# EK-TM4C1294XL_REV_D-shield.net
KiCad netlist of a schematic drawn in EAGLE
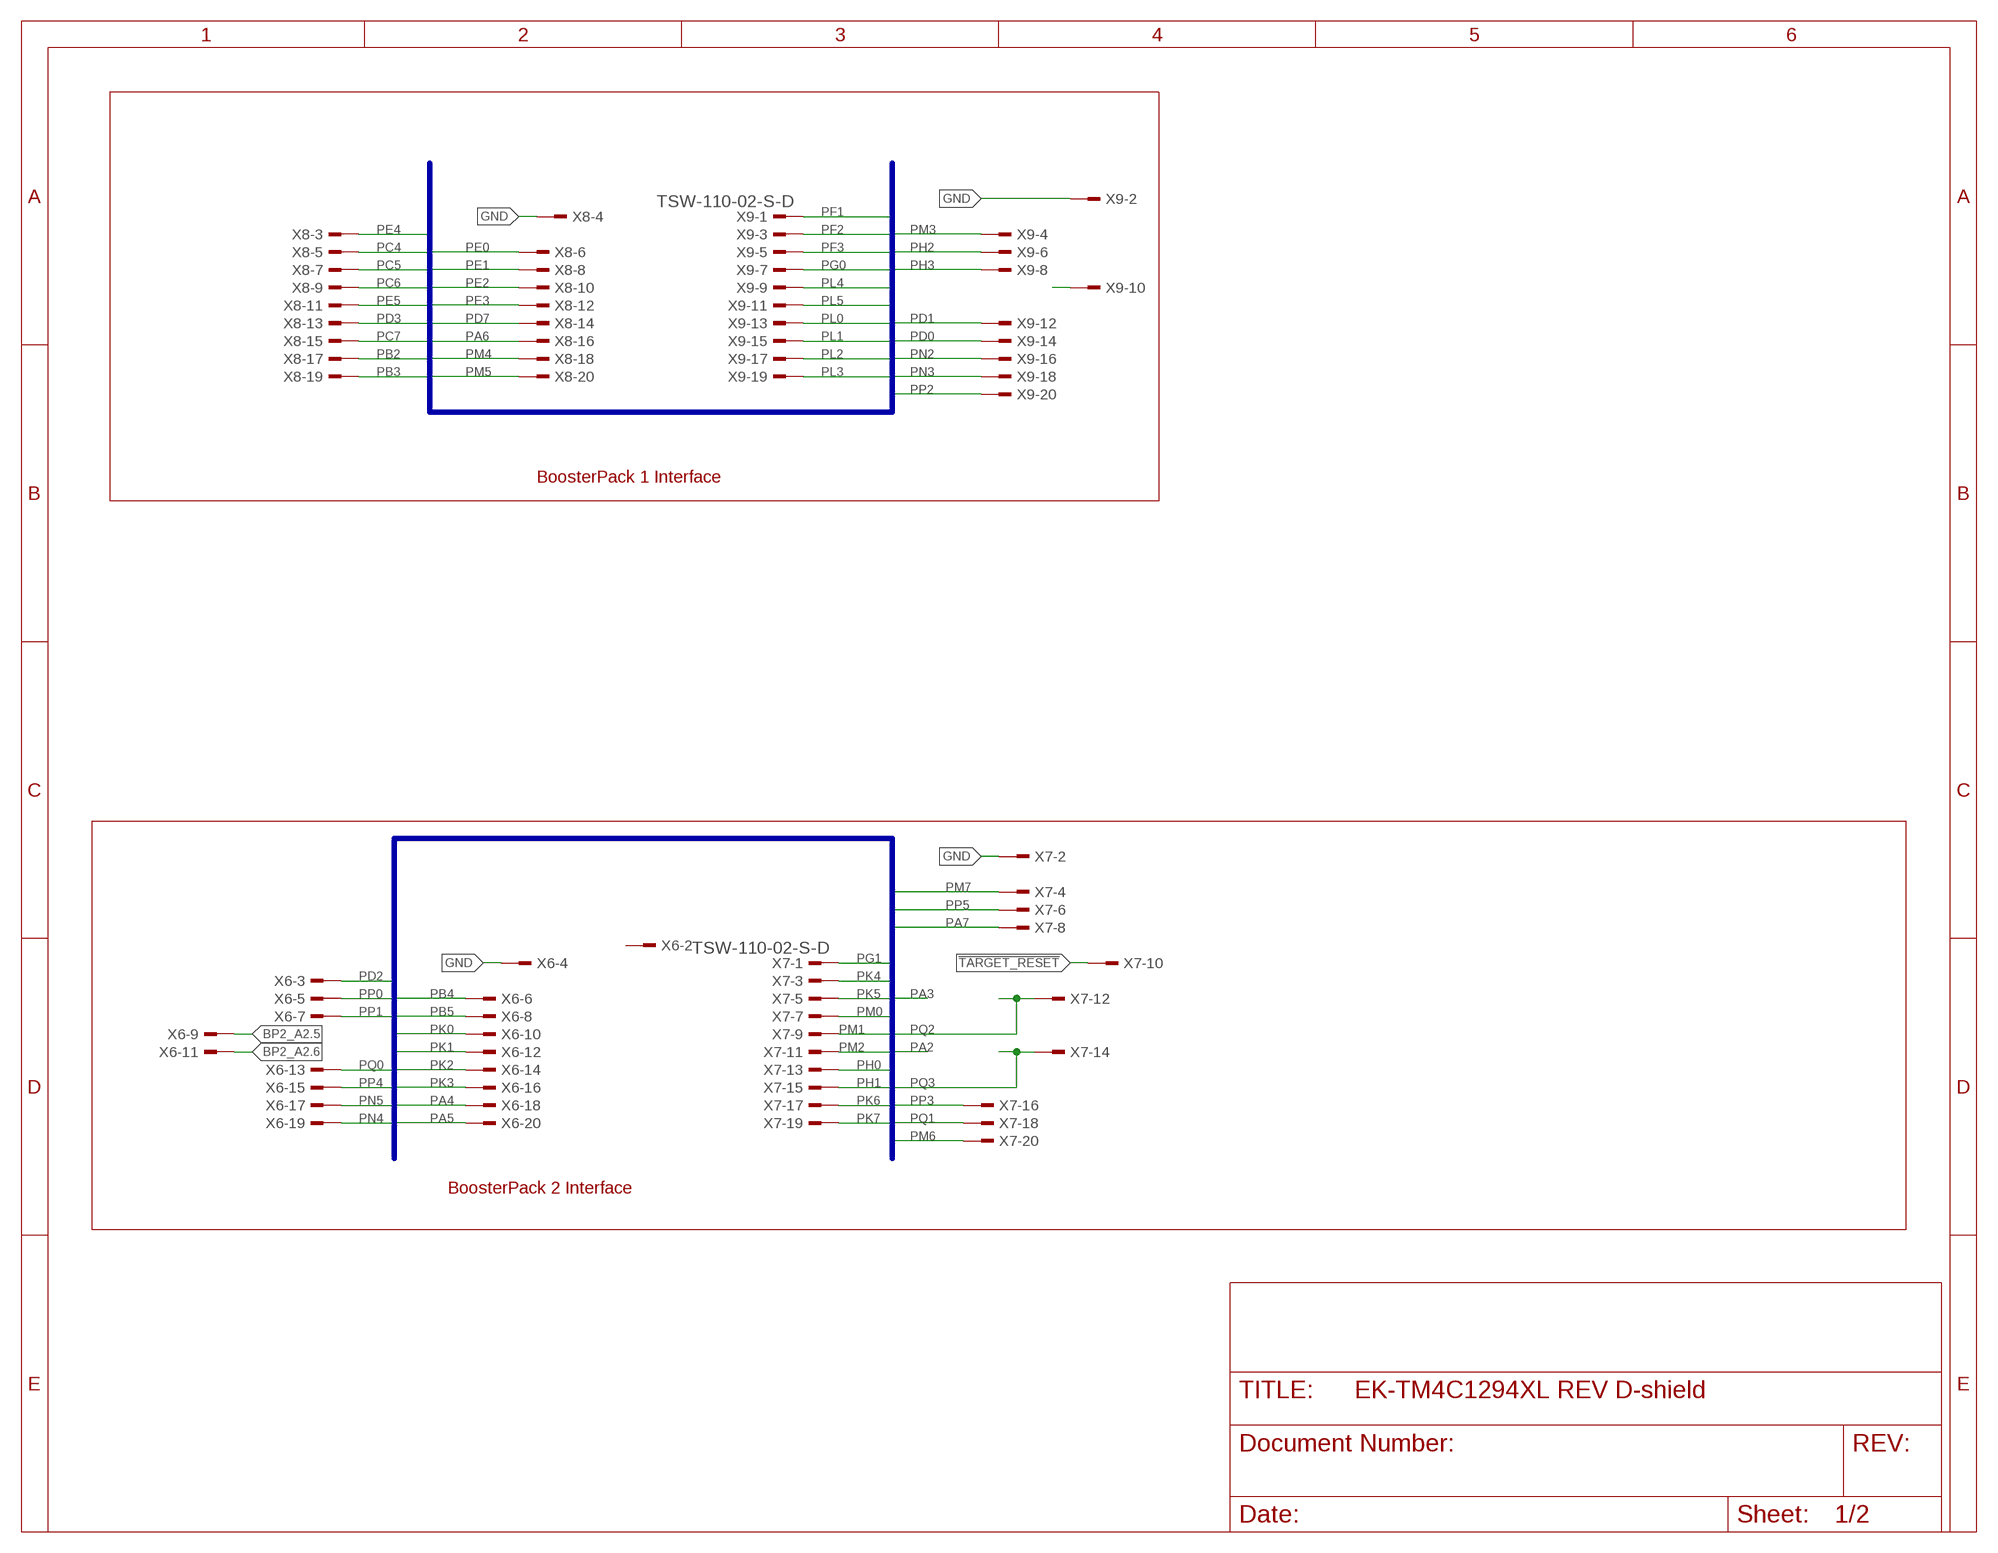
[diagram p0: schematic, sheet 1]
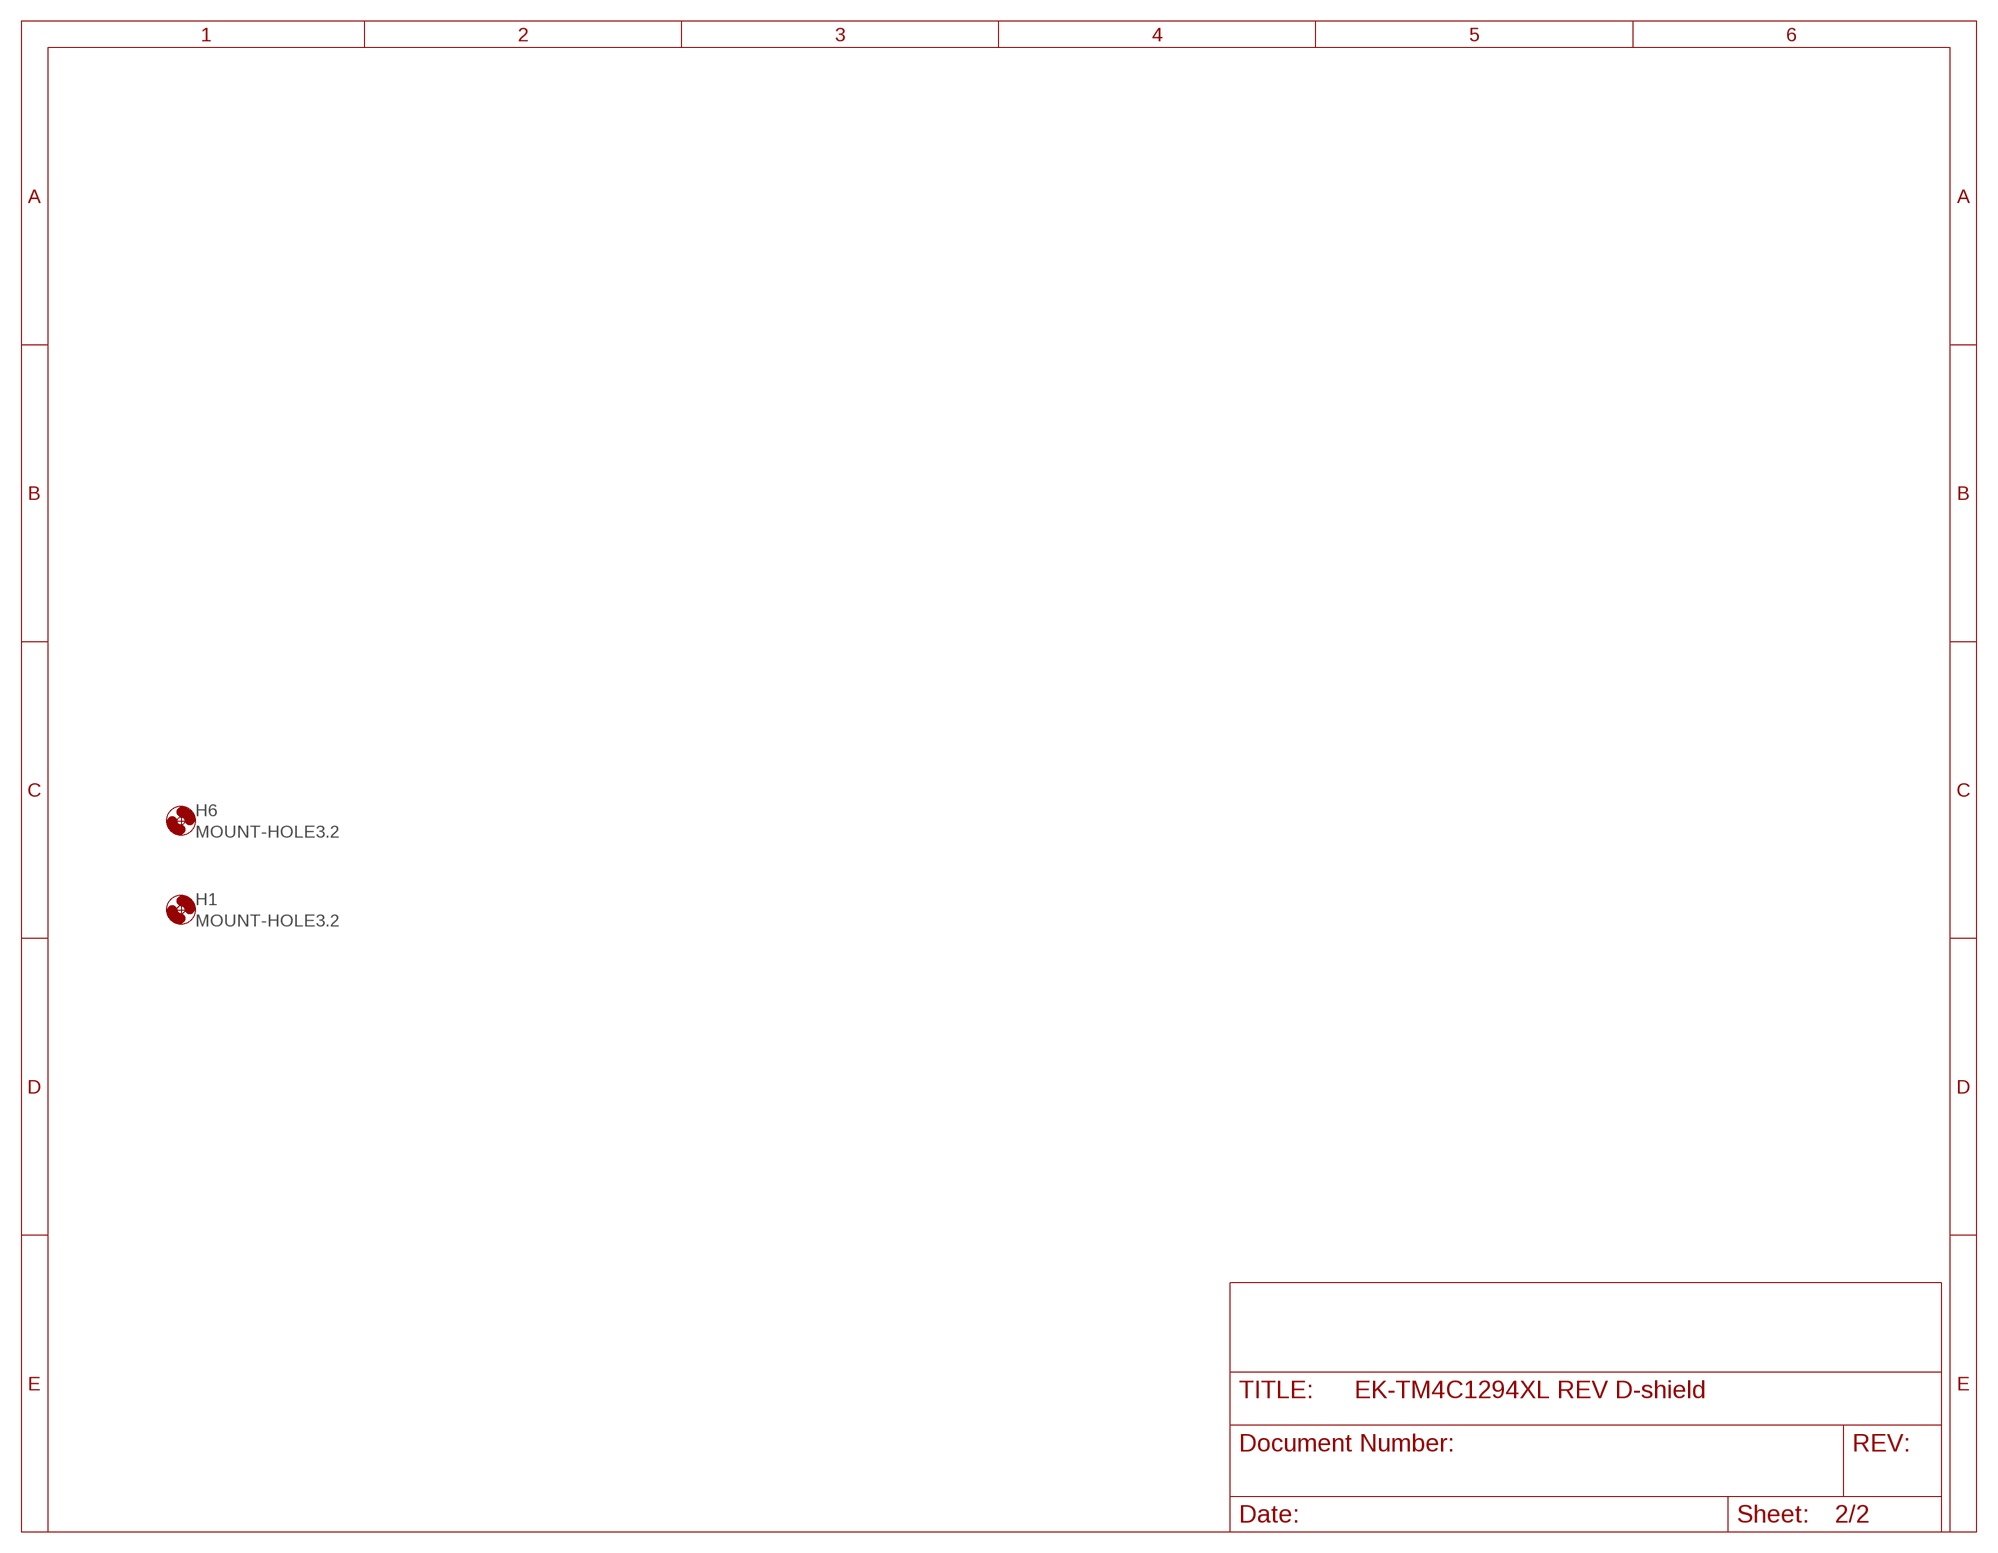
[diagram p1: schematic, sheet 2]

(export (version "E")
  (design (tool "Eeschema 10.0.6"))
  (components
    (comp (ref "H1")
      (value "MOUNT-HOLE3.2")
      (footprint "eagle-import:3,2")
      (libsource (lib "eagle-import") (part "MOUNT-HOLE3.2"))
    )
    (comp (ref "H6")
      (value "MOUNT-HOLE3.2")
      (footprint "eagle-import:3,2")
      (libsource (lib "eagle-import") (part "MOUNT-HOLE3.2"))
    )
    (comp (ref "X6")
      (value "TSW-110-02-S-D")
      (footprint "eagle-import:TSW-110-02-S-D")
      (fields (field (name "GNUM") "G22-THSTK-2X10-BAC"))
      (libsource (lib "eagle-import") (part "TSW-110-02-S-D"))
    )
    (comp (ref "X7")
      (value "TSW-110-02-S-D")
      (footprint "eagle-import:TSW-110-02-S-D")
      (fields (field (name "GNUM") "G22-THSTK-2X10-BAC"))
      (libsource (lib "eagle-import") (part "TSW-110-02-S-D"))
    )
    (comp (ref "X8")
      (value "TSW-110-02-S-D")
      (footprint "eagle-import:TSW-110-02-S-D")
      (fields (field (name "GNUM") "G22-THSTK-2X10-BAC"))
      (libsource (lib "eagle-import") (part "TSW-110-02-S-D"))
    )
    (comp (ref "X9")
      (value "TSW-110-02-S-D")
      (footprint "eagle-import:TSW-110-02-S-D")
      (fields (field (name "GNUM") "G22-THSTK-2X10-BAC"))
      (libsource (lib "eagle-import") (part "TSW-110-02-S-D"))
    )
  )
  (nets
    (net (code "1") (name "BP2_A2.5") (class "Default")
      (node (ref "X6") (pin "9") (pinfunction "1_9") (pintype "passive"))
    )
    (net (code "2") (name "BP2_A2.6") (class "Default")
      (node (ref "X6") (pin "11") (pinfunction "1_11") (pintype "passive"))
    )
    (net (code "3") (name "GND") (class "Default")
      (node (ref "X6") (pin "4") (pinfunction "1_4") (pintype "passive"))
      (node (ref "X7") (pin "2") (pinfunction "1_2") (pintype "passive"))
      (node (ref "X8") (pin "4") (pinfunction "1_4") (pintype "passive"))
      (node (ref "X9") (pin "2") (pinfunction "1_2") (pintype "passive"))
    )
    (net (code "6") (name "PA4") (class "Default")
      (node (ref "X6") (pin "18") (pinfunction "1_18") (pintype "passive"))
    )
    (net (code "7") (name "PA5") (class "Default")
      (node (ref "X6") (pin "20") (pinfunction "1_20") (pintype "passive"))
    )
    (net (code "8") (name "PA6") (class "Default")
      (node (ref "X8") (pin "16") (pinfunction "1_16") (pintype "passive"))
    )
    (net (code "9") (name "PA7") (class "Default")
      (node (ref "X7") (pin "8") (pinfunction "1_8") (pintype "passive"))
    )
    (net (code "10") (name "PB2") (class "Default")
      (node (ref "X8") (pin "17") (pinfunction "1_17") (pintype "passive"))
    )
    (net (code "11") (name "PB3") (class "Default")
      (node (ref "X8") (pin "19") (pinfunction "1_19") (pintype "passive"))
    )
    (net (code "12") (name "PB4") (class "Default")
      (node (ref "X6") (pin "6") (pinfunction "1_6") (pintype "passive"))
    )
    (net (code "13") (name "PB5") (class "Default")
      (node (ref "X6") (pin "8") (pinfunction "1_8") (pintype "passive"))
    )
    (net (code "14") (name "PC4") (class "Default")
      (node (ref "X8") (pin "5") (pinfunction "1_5") (pintype "passive"))
    )
    (net (code "15") (name "PC5") (class "Default")
      (node (ref "X8") (pin "7") (pinfunction "1_7") (pintype "passive"))
    )
    (net (code "16") (name "PC6") (class "Default")
      (node (ref "X8") (pin "9") (pinfunction "1_9") (pintype "passive"))
    )
    (net (code "17") (name "PC7") (class "Default")
      (node (ref "X8") (pin "15") (pinfunction "1_15") (pintype "passive"))
    )
    (net (code "18") (name "PD0") (class "Default")
      (node (ref "X9") (pin "14") (pinfunction "1_14") (pintype "passive"))
    )
    (net (code "19") (name "PD1") (class "Default")
      (node (ref "X9") (pin "12") (pinfunction "1_12") (pintype "passive"))
    )
    (net (code "20") (name "PD2") (class "Default")
      (node (ref "X6") (pin "3") (pinfunction "1_3") (pintype "passive"))
    )
    (net (code "21") (name "PD3") (class "Default")
      (node (ref "X8") (pin "13") (pinfunction "1_13") (pintype "passive"))
    )
    (net (code "22") (name "PD7") (class "Default")
      (node (ref "X8") (pin "14") (pinfunction "1_14") (pintype "passive"))
    )
    (net (code "23") (name "PE0") (class "Default")
      (node (ref "X8") (pin "6") (pinfunction "1_6") (pintype "passive"))
    )
    (net (code "24") (name "PE1") (class "Default")
      (node (ref "X8") (pin "8") (pinfunction "1_8") (pintype "passive"))
    )
    (net (code "25") (name "PE2") (class "Default")
      (node (ref "X8") (pin "10") (pinfunction "1_10") (pintype "passive"))
    )
    (net (code "26") (name "PE3") (class "Default")
      (node (ref "X8") (pin "12") (pinfunction "1_12") (pintype "passive"))
    )
    (net (code "27") (name "PE4") (class "Default")
      (node (ref "X8") (pin "3") (pinfunction "1_3") (pintype "passive"))
    )
    (net (code "28") (name "PE5") (class "Default")
      (node (ref "X8") (pin "11") (pinfunction "1_11") (pintype "passive"))
    )
    (net (code "29") (name "PF1") (class "Default")
      (node (ref "X9") (pin "1") (pinfunction "1_1") (pintype "passive"))
    )
    (net (code "30") (name "PF2") (class "Default")
      (node (ref "X9") (pin "3") (pinfunction "1_3") (pintype "passive"))
    )
    (net (code "31") (name "PF3") (class "Default")
      (node (ref "X9") (pin "5") (pinfunction "1_5") (pintype "passive"))
    )
    (net (code "32") (name "PG0") (class "Default")
      (node (ref "X9") (pin "7") (pinfunction "1_7") (pintype "passive"))
    )
    (net (code "33") (name "PG1") (class "Default")
      (node (ref "X7") (pin "1") (pinfunction "1_1") (pintype "passive"))
    )
    (net (code "34") (name "PH0") (class "Default")
      (node (ref "X7") (pin "13") (pinfunction "1_13") (pintype "passive"))
    )
    (net (code "35") (name "PH1") (class "Default")
      (node (ref "X7") (pin "15") (pinfunction "1_15") (pintype "passive"))
    )
    (net (code "36") (name "PH2") (class "Default")
      (node (ref "X9") (pin "6") (pinfunction "1_6") (pintype "passive"))
    )
    (net (code "37") (name "PH3") (class "Default")
      (node (ref "X9") (pin "8") (pinfunction "1_8") (pintype "passive"))
    )
    (net (code "38") (name "PK0") (class "Default")
      (node (ref "X6") (pin "10") (pinfunction "1_10") (pintype "passive"))
    )
    (net (code "39") (name "PK1") (class "Default")
      (node (ref "X6") (pin "12") (pinfunction "1_12") (pintype "passive"))
    )
    (net (code "40") (name "PK2") (class "Default")
      (node (ref "X6") (pin "14") (pinfunction "1_14") (pintype "passive"))
    )
    (net (code "41") (name "PK3") (class "Default")
      (node (ref "X6") (pin "16") (pinfunction "1_16") (pintype "passive"))
    )
    (net (code "42") (name "PK4") (class "Default")
      (node (ref "X7") (pin "3") (pinfunction "1_3") (pintype "passive"))
    )
    (net (code "43") (name "PK5") (class "Default")
      (node (ref "X7") (pin "5") (pinfunction "1_5") (pintype "passive"))
    )
    (net (code "44") (name "PK6") (class "Default")
      (node (ref "X7") (pin "17") (pinfunction "1_17") (pintype "passive"))
    )
    (net (code "45") (name "PK7") (class "Default")
      (node (ref "X7") (pin "19") (pinfunction "1_19") (pintype "passive"))
    )
    (net (code "46") (name "PL0") (class "Default")
      (node (ref "X9") (pin "13") (pinfunction "1_13") (pintype "passive"))
    )
    (net (code "47") (name "PL1") (class "Default")
      (node (ref "X9") (pin "15") (pinfunction "1_15") (pintype "passive"))
    )
    (net (code "48") (name "PL2") (class "Default")
      (node (ref "X9") (pin "17") (pinfunction "1_17") (pintype "passive"))
    )
    (net (code "49") (name "PL3") (class "Default")
      (node (ref "X9") (pin "19") (pinfunction "1_19") (pintype "passive"))
    )
    (net (code "50") (name "PL4") (class "Default")
      (node (ref "X9") (pin "9") (pinfunction "1_9") (pintype "passive"))
    )
    (net (code "51") (name "PL5") (class "Default")
      (node (ref "X9") (pin "11") (pinfunction "1_11") (pintype "passive"))
    )
    (net (code "52") (name "PM0") (class "Default")
      (node (ref "X7") (pin "7") (pinfunction "1_7") (pintype "passive"))
    )
    (net (code "53") (name "PM1") (class "Default")
      (node (ref "X7") (pin "9") (pinfunction "1_9") (pintype "passive"))
    )
    (net (code "54") (name "PM2") (class "Default")
      (node (ref "X7") (pin "11") (pinfunction "1_11") (pintype "passive"))
    )
    (net (code "55") (name "PM3") (class "Default")
      (node (ref "X9") (pin "4") (pinfunction "1_4") (pintype "passive"))
    )
    (net (code "56") (name "PM4") (class "Default")
      (node (ref "X8") (pin "18") (pinfunction "1_18") (pintype "passive"))
    )
    (net (code "57") (name "PM5") (class "Default")
      (node (ref "X8") (pin "20") (pinfunction "1_20") (pintype "passive"))
    )
    (net (code "58") (name "PM6") (class "Default")
      (node (ref "X7") (pin "20") (pinfunction "1_20") (pintype "passive"))
    )
    (net (code "59") (name "PM7") (class "Default")
      (node (ref "X7") (pin "4") (pinfunction "1_4") (pintype "passive"))
    )
    (net (code "60") (name "PN2") (class "Default")
      (node (ref "X9") (pin "16") (pinfunction "1_16") (pintype "passive"))
    )
    (net (code "61") (name "PN3") (class "Default")
      (node (ref "X9") (pin "18") (pinfunction "1_18") (pintype "passive"))
    )
    (net (code "62") (name "PN4") (class "Default")
      (node (ref "X6") (pin "19") (pinfunction "1_19") (pintype "passive"))
    )
    (net (code "63") (name "PN5") (class "Default")
      (node (ref "X6") (pin "17") (pinfunction "1_17") (pintype "passive"))
    )
    (net (code "64") (name "PP0") (class "Default")
      (node (ref "X6") (pin "5") (pinfunction "1_5") (pintype "passive"))
    )
    (net (code "65") (name "PP1") (class "Default")
      (node (ref "X6") (pin "7") (pinfunction "1_7") (pintype "passive"))
    )
    (net (code "66") (name "PP2") (class "Default")
      (node (ref "X9") (pin "20") (pinfunction "1_20") (pintype "passive"))
    )
    (net (code "67") (name "PP3") (class "Default")
      (node (ref "X7") (pin "16") (pinfunction "1_16") (pintype "passive"))
    )
    (net (code "68") (name "PP4") (class "Default")
      (node (ref "X6") (pin "15") (pinfunction "1_15") (pintype "passive"))
    )
    (net (code "69") (name "PP5") (class "Default")
      (node (ref "X7") (pin "6") (pinfunction "1_6") (pintype "passive"))
    )
    (net (code "70") (name "PQ0") (class "Default")
      (node (ref "X6") (pin "13") (pinfunction "1_13") (pintype "passive"))
    )
    (net (code "71") (name "PQ1") (class "Default")
      (node (ref "X7") (pin "18") (pinfunction "1_18") (pintype "passive"))
    )
    (net (code "72") (name "PQ2") (class "Default")
      (node (ref "X7") (pin "12") (pinfunction "1_12") (pintype "passive"))
    )
    (net (code "73") (name "PQ3") (class "Default")
      (node (ref "X7") (pin "14") (pinfunction "1_14") (pintype "passive"))
    )
    (net (code "74") (name "unconnected-(X6L-1-Pad2)") (class "Default")
      (node (ref "X6") (pin "2") (pinfunction "1_2") (pintype "passive"))
    )
    (net (code "75") (name "~{TARGET_RESET}") (class "Default")
      (node (ref "X7") (pin "10") (pinfunction "1_10") (pintype "passive"))
      (node (ref "X9") (pin "10") (pinfunction "1_10") (pintype "passive"))
    )
  )
)
